# design.net
KiCad netlist of a schematic drawn in Altium Designer
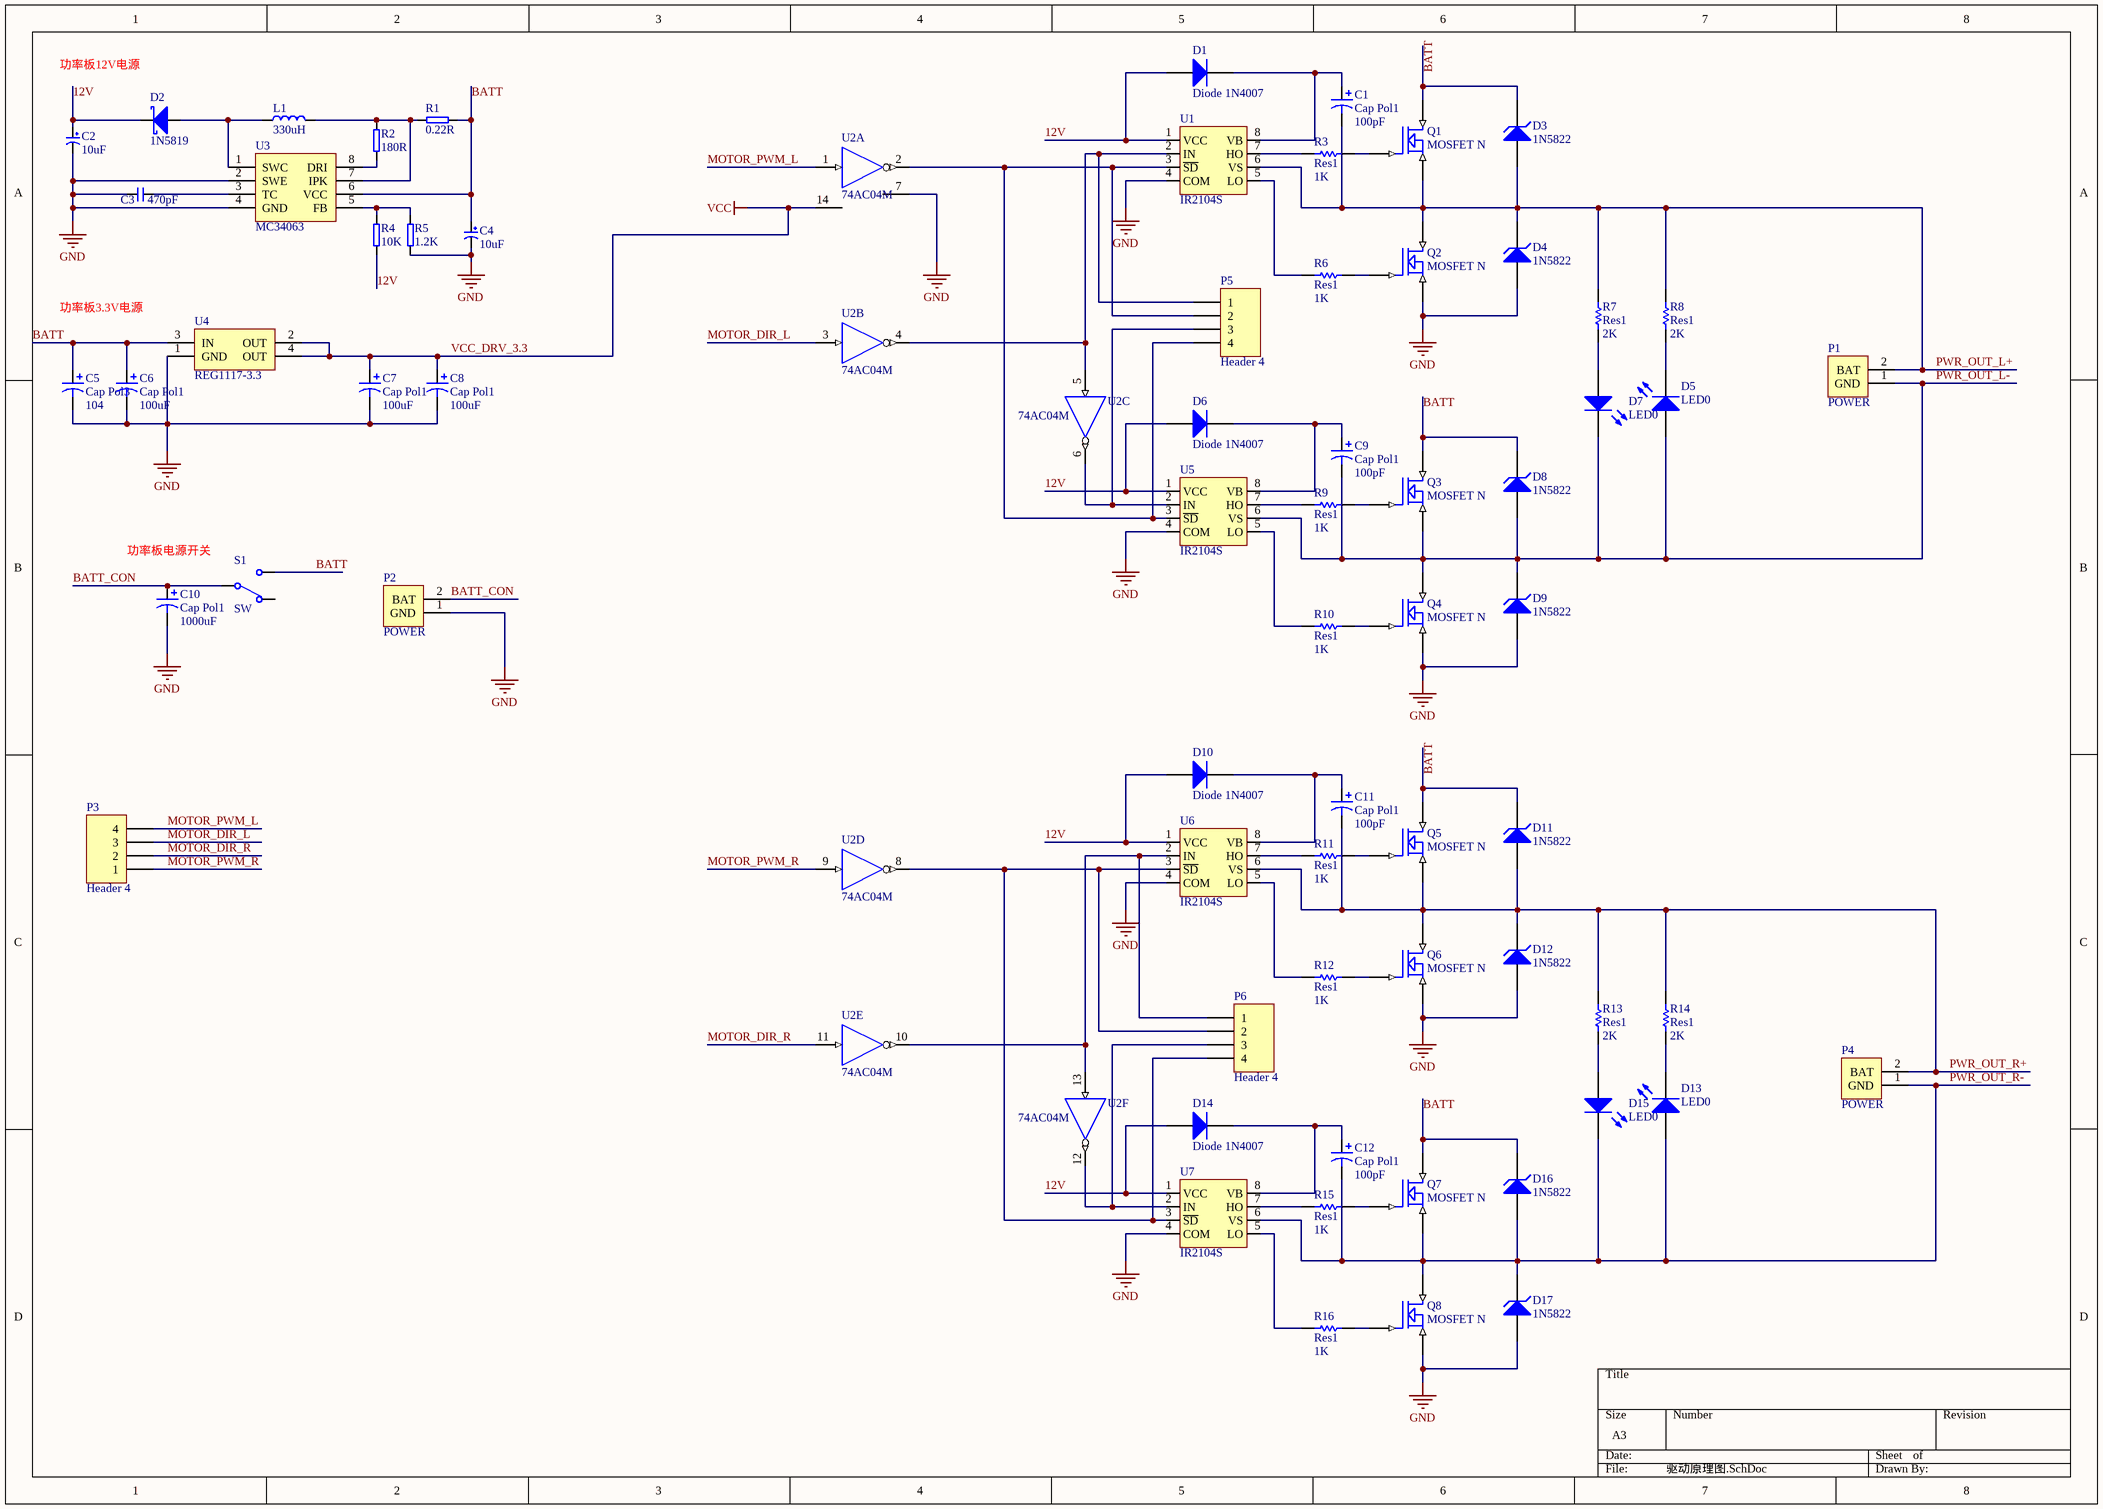
[diagram p0: 驱动原理图.SchDoc]

(export (version "E")
  (design (tool "Eeschema 10.0.6"))
  (components
    (comp (ref "C1")
      (value "Cap Pol1")
      (footprint "C0805")
      (description "Polarized Capacitor (Radial)")
      (fields (field (name "ALTIUM_VALUE") "100pF") (field (name "PUBLISHER") "Altium Limited"))
      (libsource (lib "Miscellaneous Devices") (part "Cap Pol1"))
    )
    (comp (ref "C2")
      (value "10uF")
      (footprint "3216-CAP-TA")
      (libsource (lib "2017elec_Library") (part "CAP_TA_3216"))
    )
    (comp (ref "C3")
      (value "470pF")
      (footprint "0603-CAP")
      (libsource (lib "2017elec_Library") (part "CAP_0603"))
    )
    (comp (ref "C4")
      (value "10uF")
      (footprint "3216-CAP-TA")
      (libsource (lib "2017elec_Library") (part "CAP_TA_3216"))
    )
    (comp (ref "C5")
      (value "Cap Pol3")
      (footprint "0805")
      (description "Polarized Capacitor (Surface Mount)")
      (fields (field (name "ALTIUM_VALUE") "104") (field (name "PUBLISHER") "Altium Limited"))
      (libsource (lib "Miscellaneous Devices") (part "Cap Pol3"))
    )
    (comp (ref "C6")
      (value "Cap Pol1")
      (footprint "RB.1/.2 - duplicate")
      (description "Polarized Capacitor (Radial)")
      (fields (field (name "ALTIUM_VALUE") "100uF") (field (name "PUBLISHER") "Altium Limited"))
      (libsource (lib "Miscellaneous Devices") (part "Cap Pol1"))
    )
    (comp (ref "C7")
      (value "Cap Pol1")
      (footprint "RB.1/.2 - duplicate")
      (description "Polarized Capacitor (Radial)")
      (fields (field (name "ALTIUM_VALUE") "100uF") (field (name "PUBLISHER") "Altium Limited"))
      (libsource (lib "Miscellaneous Devices") (part "Cap Pol1"))
    )
    (comp (ref "C8")
      (value "Cap Pol1")
      (footprint "RB.1/.2 - duplicate")
      (description "Polarized Capacitor (Radial)")
      (fields (field (name "ALTIUM_VALUE") "100uF") (field (name "PUBLISHER") "Altium Limited"))
      (libsource (lib "Miscellaneous Devices") (part "Cap Pol1"))
    )
    (comp (ref "C9")
      (value "Cap Pol1")
      (footprint "C0805")
      (description "Polarized Capacitor (Radial)")
      (fields (field (name "ALTIUM_VALUE") "100pF") (field (name "PUBLISHER") "Altium Limited"))
      (libsource (lib "Miscellaneous Devices") (part "Cap Pol1"))
    )
    (comp (ref "C10")
      (value "Cap Pol1")
      (footprint "CAPP")
      (description "Polarized Capacitor (Radial)")
      (fields (field (name "ALTIUM_VALUE") "1000uF") (field (name "PUBLISHER") "Altium Limited"))
      (libsource (lib "Miscellaneous Devices") (part "Cap Pol1"))
    )
    (comp (ref "C11")
      (value "Cap Pol1")
      (footprint "C0805")
      (description "Polarized Capacitor (Radial)")
      (fields (field (name "ALTIUM_VALUE") "100pF") (field (name "PUBLISHER") "Altium Limited"))
      (libsource (lib "Miscellaneous Devices") (part "Cap Pol1"))
    )
    (comp (ref "C12")
      (value "Cap Pol1")
      (footprint "C0805")
      (description "Polarized Capacitor (Radial)")
      (fields (field (name "ALTIUM_VALUE") "100pF") (field (name "PUBLISHER") "Altium Limited"))
      (libsource (lib "Miscellaneous Devices") (part "Cap Pol1"))
    )
    (comp (ref "D1")
      (value "Diode 1N4007")
      (footprint "DO-214AC(SMA)-SBD")
      (description "1 Amp General Purpose Rectifier")
      (fields (field (name "PUBLISHER") "Altium Limited"))
      (libsource (lib "Miscellaneous Devices") (part "Diode 1N4007"))
    )
    (comp (ref "D2")
      (value "1N5819")
      (footprint "DO-214AC(SMA)-SBD")
      (libsource (lib "2017elec_Library") (part "1N5819"))
    )
    (comp (ref "D3")
      (value "1N5822")
      (footprint "DO-214AC(SMA)-SBD")
      (description "One Watt Hermetically Sealed Glass Silicon Zener Diode")
      (fields (field (name "PUBLISHER") "Altium Limited"))
      (libsource (lib "Motorola Discrete Diode") (part "1N4760A"))
    )
    (comp (ref "D4")
      (value "1N5822")
      (footprint "DO-214AC(SMA)-SBD")
      (description "One Watt Hermetically Sealed Glass Silicon Zener Diode")
      (fields (field (name "PUBLISHER") "Altium Limited"))
      (libsource (lib "Motorola Discrete Diode") (part "1N4760A"))
    )
    (comp (ref "D5")
      (value "LED0")
      (footprint "3.5X2.8X1.9")
      (description "Typical INFRARED GaAs LED")
      (fields (field (name "PUBLISHER") "Altium Limited"))
      (libsource (lib "Miscellaneous Devices") (part "LED0"))
    )
    (comp (ref "D6")
      (value "Diode 1N4007")
      (footprint "DO-214AC(SMA)-SBD")
      (description "1 Amp General Purpose Rectifier")
      (fields (field (name "PUBLISHER") "Altium Limited"))
      (libsource (lib "Miscellaneous Devices") (part "Diode 1N4007"))
    )
    (comp (ref "D7")
      (value "LED0")
      (footprint "3.5X2.8X1.9")
      (description "Typical INFRARED GaAs LED")
      (fields (field (name "PUBLISHER") "Altium Limited"))
      (libsource (lib "Miscellaneous Devices") (part "LED0"))
    )
    (comp (ref "D8")
      (value "1N5822")
      (footprint "DO-214AC(SMA)-SBD")
      (description "One Watt Hermetically Sealed Glass Silicon Zener Diode")
      (fields (field (name "PUBLISHER") "Altium Limited"))
      (libsource (lib "Motorola Discrete Diode") (part "1N4760A"))
    )
    (comp (ref "D9")
      (value "1N5822")
      (footprint "DO-214AC(SMA)-SBD")
      (description "One Watt Hermetically Sealed Glass Silicon Zener Diode")
      (fields (field (name "PUBLISHER") "Altium Limited"))
      (libsource (lib "Motorola Discrete Diode") (part "1N4760A"))
    )
    (comp (ref "D10")
      (value "Diode 1N4007")
      (footprint "DO-214AC(SMA)-SBD")
      (description "1 Amp General Purpose Rectifier")
      (fields (field (name "PUBLISHER") "Altium Limited"))
      (libsource (lib "Miscellaneous Devices") (part "Diode 1N4007"))
    )
    (comp (ref "D11")
      (value "1N5822")
      (footprint "DO-214AC(SMA)-SBD")
      (description "One Watt Hermetically Sealed Glass Silicon Zener Diode")
      (fields (field (name "PUBLISHER") "Altium Limited"))
      (libsource (lib "Motorola Discrete Diode") (part "1N4760A"))
    )
    (comp (ref "D12")
      (value "1N5822")
      (footprint "DO-214AC(SMA)-SBD")
      (description "One Watt Hermetically Sealed Glass Silicon Zener Diode")
      (fields (field (name "PUBLISHER") "Altium Limited"))
      (libsource (lib "Motorola Discrete Diode") (part "1N4760A"))
    )
    (comp (ref "D13")
      (value "LED0")
      (footprint "3.5X2.8X1.9")
      (description "Typical INFRARED GaAs LED")
      (fields (field (name "PUBLISHER") "Altium Limited"))
      (libsource (lib "Miscellaneous Devices") (part "LED0"))
    )
    (comp (ref "D14")
      (value "Diode 1N4007")
      (footprint "DO-214AC(SMA)-SBD")
      (description "1 Amp General Purpose Rectifier")
      (fields (field (name "PUBLISHER") "Altium Limited"))
      (libsource (lib "Miscellaneous Devices") (part "Diode 1N4007"))
    )
    (comp (ref "D15")
      (value "LED0")
      (footprint "3.5X2.8X1.9")
      (description "Typical INFRARED GaAs LED")
      (fields (field (name "PUBLISHER") "Altium Limited"))
      (libsource (lib "Miscellaneous Devices") (part "LED0"))
    )
    (comp (ref "D16")
      (value "1N5822")
      (footprint "DO-214AC(SMA)-SBD")
      (description "One Watt Hermetically Sealed Glass Silicon Zener Diode")
      (fields (field (name "PUBLISHER") "Altium Limited"))
      (libsource (lib "Motorola Discrete Diode") (part "1N4760A"))
    )
    (comp (ref "D17")
      (value "1N5822")
      (footprint "DO-214AC(SMA)-SBD")
      (description "One Watt Hermetically Sealed Glass Silicon Zener Diode")
      (fields (field (name "PUBLISHER") "Altium Limited"))
      (libsource (lib "Motorola Discrete Diode") (part "1N4760A"))
    )
    (comp (ref "L1")
      (value "330uH")
      (footprint "Inductor_7*7*4")
      (libsource (lib "2017elec_Library") (part "inductor_7*7*4"))
    )
    (comp (ref "P1") (value "POWER") (footprint "POWER") (libsource (lib "2017elec_Library") (part "POWER")))
    (comp (ref "P2") (value "POWER") (footprint "POWER") (libsource (lib "2017elec_Library") (part "POWER")))
    (comp (ref "P3")
      (value "Header 4")
      (footprint "HDR1X4")
      (description "Header, 4-Pin")
      (fields (field (name "PUBLISHER") "Altium Limited"))
      (libsource (lib "Miscellaneous Connectors") (part "Header 4"))
    )
    (comp (ref "P4") (value "POWER") (footprint "POWER") (libsource (lib "2017elec_Library") (part "POWER")))
    (comp (ref "P5")
      (value "Header 4")
      (footprint "HDR1X4")
      (description "Header, 4-Pin")
      (fields (field (name "PUBLISHER") "Altium Limited"))
      (libsource (lib "") (part "Header 4_1"))
    )
    (comp (ref "P6")
      (value "Header 4")
      (footprint "HDR1X4")
      (description "Header, 4-Pin")
      (fields (field (name "PUBLISHER") "Altium Limited"))
      (libsource (lib "") (part "Header 4_1"))
    )
    (comp (ref "Q1") (value "MOSFET N") (footprint "TO-252") (libsource (lib "场效应管及可控硅") (part "MOSFET N")))
    (comp (ref "Q2") (value "MOSFET N") (footprint "TO-252") (libsource (lib "场效应管及可控硅") (part "MOSFET N")))
    (comp (ref "Q3") (value "MOSFET N") (footprint "TO-252") (libsource (lib "场效应管及可控硅") (part "MOSFET N")))
    (comp (ref "Q4") (value "MOSFET N") (footprint "TO-252") (libsource (lib "场效应管及可控硅") (part "MOSFET N")))
    (comp (ref "Q5") (value "MOSFET N") (footprint "TO-252") (libsource (lib "场效应管及可控硅") (part "MOSFET N")))
    (comp (ref "Q6") (value "MOSFET N") (footprint "TO-252") (libsource (lib "场效应管及可控硅") (part "MOSFET N")))
    (comp (ref "Q7") (value "MOSFET N") (footprint "TO-252") (libsource (lib "场效应管及可控硅") (part "MOSFET N")))
    (comp (ref "Q8") (value "MOSFET N") (footprint "TO-252") (libsource (lib "场效应管及可控硅") (part "MOSFET N")))
    (comp (ref "R1")
      (value "0.22R")
      (footprint "0603-RES")
      (libsource (lib "2017elec_Library") (part "RES_0603"))
    )
    (comp (ref "R2")
      (value "180R")
      (footprint "0603-RES")
      (libsource (lib "2017elec_Library") (part "RES_0603"))
    )
    (comp (ref "R3")
      (value "Res1")
      (footprint "0603-RES")
      (description "Resistor")
      (fields (field (name "ALTIUM_VALUE") "1K") (field (name "PUBLISHER") "Altium Limited"))
      (libsource (lib "Miscellaneous Devices") (part "Res1"))
    )
    (comp (ref "R4")
      (value "10K")
      (footprint "0603-RES")
      (libsource (lib "2017elec_Library") (part "RES_0603"))
    )
    (comp (ref "R5")
      (value "1.2K")
      (footprint "0603-RES")
      (libsource (lib "2017elec_Library") (part "RES_0603"))
    )
    (comp (ref "R6")
      (value "Res1")
      (footprint "0603-RES")
      (description "Resistor")
      (fields (field (name "ALTIUM_VALUE") "1K") (field (name "PUBLISHER") "Altium Limited"))
      (libsource (lib "Miscellaneous Devices") (part "Res1"))
    )
    (comp (ref "R7")
      (value "Res1")
      (footprint "0603-RES")
      (description "Resistor")
      (fields (field (name "ALTIUM_VALUE") "2K") (field (name "PUBLISHER") "Altium Limited"))
      (libsource (lib "Miscellaneous Devices") (part "Res1"))
    )
    (comp (ref "R8")
      (value "Res1")
      (footprint "0603-RES")
      (description "Resistor")
      (fields (field (name "ALTIUM_VALUE") "2K") (field (name "PUBLISHER") "Altium Limited"))
      (libsource (lib "Miscellaneous Devices") (part "Res1"))
    )
    (comp (ref "R9")
      (value "Res1")
      (footprint "0603-RES")
      (description "Resistor")
      (fields (field (name "ALTIUM_VALUE") "1K") (field (name "PUBLISHER") "Altium Limited"))
      (libsource (lib "Miscellaneous Devices") (part "Res1"))
    )
    (comp (ref "R10")
      (value "Res1")
      (footprint "0603-RES")
      (description "Resistor")
      (fields (field (name "ALTIUM_VALUE") "1K") (field (name "PUBLISHER") "Altium Limited"))
      (libsource (lib "Miscellaneous Devices") (part "Res1"))
    )
    (comp (ref "R11")
      (value "Res1")
      (footprint "0603-RES")
      (description "Resistor")
      (fields (field (name "ALTIUM_VALUE") "1K") (field (name "PUBLISHER") "Altium Limited"))
      (libsource (lib "Miscellaneous Devices") (part "Res1"))
    )
    (comp (ref "R12")
      (value "Res1")
      (footprint "0603-RES")
      (description "Resistor")
      (fields (field (name "ALTIUM_VALUE") "1K") (field (name "PUBLISHER") "Altium Limited"))
      (libsource (lib "Miscellaneous Devices") (part "Res1"))
    )
    (comp (ref "R13")
      (value "Res1")
      (footprint "0603-RES")
      (description "Resistor")
      (fields (field (name "ALTIUM_VALUE") "2K") (field (name "PUBLISHER") "Altium Limited"))
      (libsource (lib "Miscellaneous Devices") (part "Res1"))
    )
    (comp (ref "R14")
      (value "Res1")
      (footprint "0603-CAP")
      (description "Resistor")
      (fields (field (name "ALTIUM_VALUE") "2K") (field (name "PUBLISHER") "Altium Limited"))
      (libsource (lib "Miscellaneous Devices") (part "Res1"))
    )
    (comp (ref "R15")
      (value "Res1")
      (footprint "0603-RES")
      (description "Resistor")
      (fields (field (name "ALTIUM_VALUE") "1K") (field (name "PUBLISHER") "Altium Limited"))
      (libsource (lib "Miscellaneous Devices") (part "Res1"))
    )
    (comp (ref "R16")
      (value "Res1")
      (footprint "0603-RES")
      (description "Resistor")
      (fields (field (name "ALTIUM_VALUE") "1K") (field (name "PUBLISHER") "Altium Limited"))
      (libsource (lib "Miscellaneous Devices") (part "Res1"))
    )
    (comp (ref "S1") (value "SW") (footprint "SW") (libsource (lib "My K60") (part "SW")))
    (comp (ref "U1") (value "IR2104S") (footprint "SOIC-8") (libsource (lib "My K60") (part "IR2104S")))
    (comp (ref "U2")
      (value "74AC04M")
      (footprint "SO14_L")
      (description "Hex Inverter")
      (fields (field (name "PUBLISHER") "Altium Limited"))
      (libsource (lib "ST Logic Gate") (part "74AC04M"))
    )
    (comp (ref "U3")
      (value "MC34063")
      (footprint "SOP-8")
      (libsource (lib "2017elec_Library") (part "MC34063"))
    )
    (comp (ref "U4")
      (value "REG1117-3.3")
      (footprint "ZZ311")
      (description "800mA and 1A Low Dropout Positive Regulator 2.85V, 3.3V, 5V, and Adjustable")
      (fields (field (name "PUBLISHER") "Altium Limited"))
      (libsource (lib "BB Power Mgt Voltage Regulator") (part "REG1117-3.3"))
    )
    (comp (ref "U5") (value "IR2104S") (footprint "SOIC-8") (libsource (lib "My K60") (part "IR2104S")))
    (comp (ref "U6") (value "IR2104S") (footprint "SOIC-8") (libsource (lib "My K60") (part "IR2104S")))
    (comp (ref "U7") (value "IR2104S") (footprint "SOIC-8") (libsource (lib "My K60") (part "IR2104S")))
  )
  (nets
    (net (code "1") (name "/12V") (class "Default")
      (node (ref "C2") (pin "1") (pinfunction "1_1") (pintype "passive"))
      (node (ref "D1") (pin "1") (pinfunction "A_1") (pintype "passive"))
      (node (ref "D10") (pin "1") (pinfunction "A_1") (pintype "passive"))
      (node (ref "D14") (pin "1") (pinfunction "A_1") (pintype "passive"))
      (node (ref "D2") (pin "2") (pinfunction "K_2") (pintype "passive"))
      (node (ref "D6") (pin "1") (pinfunction "A_1") (pintype "passive"))
      (node (ref "R4") (pin "1") (pinfunction "1_1") (pintype "passive"))
      (node (ref "U1") (pin "1") (pinfunction "VCC_1") (pintype "passive"))
      (node (ref "U5") (pin "1") (pinfunction "VCC_1") (pintype "passive"))
      (node (ref "U6") (pin "1") (pinfunction "VCC_1") (pintype "passive"))
      (node (ref "U7") (pin "1") (pinfunction "VCC_1") (pintype "passive"))
    )
    (net (code "2") (name "/BATT") (class "Default")
      (node (ref "C4") (pin "1") (pinfunction "1_1") (pintype "passive"))
      (node (ref "C5") (pin "1") (pinfunction "1_1") (pintype "passive"))
      (node (ref "C6") (pin "1") (pinfunction "1_1") (pintype "passive"))
      (node (ref "D16") (pin "2") (pinfunction "K_2") (pintype "passive"))
      (node (ref "D8") (pin "2") (pinfunction "K_2") (pintype "passive"))
      (node (ref "Q3") (pin "2") (pinfunction "D_2") (pintype "input"))
      (node (ref "Q7") (pin "2") (pinfunction "D_2") (pintype "input"))
      (node (ref "R1") (pin "2") (pinfunction "2_2") (pintype "passive"))
      (node (ref "S1") (pin "3") (pinfunction "3_3") (pintype "passive"))
      (node (ref "U3") (pin "6") (pinfunction "VCC_6") (pintype "passive"))
      (node (ref "U4") (pin "3") (pinfunction "IN_3") (pintype "power_in"))
    )
    (net (code "3") (name "/BATT_CON") (class "Default")
      (node (ref "C10") (pin "1") (pinfunction "1_1") (pintype "passive"))
      (node (ref "P2") (pin "2") (pinfunction "BAT_2") (pintype "passive"))
      (node (ref "S1") (pin "2") (pinfunction "2_2") (pintype "passive"))
    )
    (net (code "4") (name "/MOTOR_DIR_L") (class "Default")
      (node (ref "P3") (pin "3") (pinfunction "3_3") (pintype "passive"))
      (node (ref "U2") (pin "3") (pinfunction "A_3") (pintype "input"))
    )
    (net (code "5") (name "/MOTOR_DIR_R") (class "Default")
      (node (ref "P3") (pin "2") (pinfunction "2_2") (pintype "passive"))
      (node (ref "U2") (pin "11") (pinfunction "A_11") (pintype "input"))
    )
    (net (code "6") (name "/MOTOR_PWM_L") (class "Default")
      (node (ref "P3") (pin "4") (pinfunction "4_4") (pintype "passive"))
      (node (ref "U2") (pin "1") (pinfunction "A_1") (pintype "input"))
    )
    (net (code "7") (name "/MOTOR_PWM_R") (class "Default")
      (node (ref "P3") (pin "1") (pinfunction "1_1") (pintype "passive"))
      (node (ref "U2") (pin "9") (pinfunction "A_9") (pintype "input"))
    )
    (net (code "8") (name "/PWR_OUT_L+") (class "Default")
      (node (ref "C1") (pin "2") (pinfunction "2_2") (pintype "passive"))
      (node (ref "D3") (pin "1") (pinfunction "A_1") (pintype "passive"))
      (node (ref "D4") (pin "2") (pinfunction "K_2") (pintype "passive"))
      (node (ref "P1") (pin "2") (pinfunction "BAT_2") (pintype "passive"))
      (node (ref "Q1") (pin "3") (pinfunction "S_3") (pintype "input"))
      (node (ref "Q2") (pin "2") (pinfunction "D_2") (pintype "input"))
      (node (ref "R7") (pin "2") (pinfunction "2_2") (pintype "passive"))
      (node (ref "R8") (pin "2") (pinfunction "2_2") (pintype "passive"))
      (node (ref "U1") (pin "6") (pinfunction "VS_6") (pintype "passive"))
    )
    (net (code "9") (name "/PWR_OUT_L-") (class "Default")
      (node (ref "C9") (pin "2") (pinfunction "2_2") (pintype "passive"))
      (node (ref "D5") (pin "1") (pinfunction "A_1") (pintype "passive"))
      (node (ref "D7") (pin "2") (pinfunction "K_2") (pintype "passive"))
      (node (ref "D8") (pin "1") (pinfunction "A_1") (pintype "passive"))
      (node (ref "D9") (pin "2") (pinfunction "K_2") (pintype "passive"))
      (node (ref "P1") (pin "1") (pinfunction "GND_1") (pintype "passive"))
      (node (ref "Q3") (pin "3") (pinfunction "S_3") (pintype "input"))
      (node (ref "Q4") (pin "2") (pinfunction "D_2") (pintype "input"))
      (node (ref "U5") (pin "6") (pinfunction "VS_6") (pintype "passive"))
    )
    (net (code "10") (name "/PWR_OUT_R+") (class "Default")
      (node (ref "C11") (pin "2") (pinfunction "2_2") (pintype "passive"))
      (node (ref "D11") (pin "1") (pinfunction "A_1") (pintype "passive"))
      (node (ref "D12") (pin "2") (pinfunction "K_2") (pintype "passive"))
      (node (ref "P4") (pin "2") (pinfunction "BAT_2") (pintype "passive"))
      (node (ref "Q5") (pin "3") (pinfunction "S_3") (pintype "input"))
      (node (ref "Q6") (pin "2") (pinfunction "D_2") (pintype "input"))
      (node (ref "R13") (pin "2") (pinfunction "2_2") (pintype "passive"))
      (node (ref "R14") (pin "2") (pinfunction "2_2") (pintype "passive"))
      (node (ref "U6") (pin "6") (pinfunction "VS_6") (pintype "passive"))
    )
    (net (code "11") (name "/PWR_OUT_R-") (class "Default")
      (node (ref "C12") (pin "2") (pinfunction "2_2") (pintype "passive"))
      (node (ref "D13") (pin "1") (pinfunction "A_1") (pintype "passive"))
      (node (ref "D15") (pin "2") (pinfunction "K_2") (pintype "passive"))
      (node (ref "D16") (pin "1") (pinfunction "A_1") (pintype "passive"))
      (node (ref "D17") (pin "2") (pinfunction "K_2") (pintype "passive"))
      (node (ref "P4") (pin "1") (pinfunction "GND_1") (pintype "passive"))
      (node (ref "Q7") (pin "3") (pinfunction "S_3") (pintype "input"))
      (node (ref "Q8") (pin "2") (pinfunction "D_2") (pintype "input"))
      (node (ref "U7") (pin "6") (pinfunction "VS_6") (pintype "passive"))
    )
    (net (code "12") (name "GND") (class "Default")
      (node (ref "C10") (pin "2") (pinfunction "2_2") (pintype "passive"))
      (node (ref "C2") (pin "2") (pinfunction "2_2") (pintype "passive"))
      (node (ref "C3") (pin "1") (pinfunction "1_1") (pintype "passive"))
      (node (ref "C4") (pin "2") (pinfunction "2_2") (pintype "passive"))
      (node (ref "C5") (pin "2") (pinfunction "2_2") (pintype "passive"))
      (node (ref "C6") (pin "2") (pinfunction "2_2") (pintype "passive"))
      (node (ref "C7") (pin "2") (pinfunction "2_2") (pintype "passive"))
      (node (ref "C8") (pin "2") (pinfunction "2_2") (pintype "passive"))
      (node (ref "D12") (pin "1") (pinfunction "A_1") (pintype "passive"))
      (node (ref "D17") (pin "1") (pinfunction "A_1") (pintype "passive"))
      (node (ref "D4") (pin "1") (pinfunction "A_1") (pintype "passive"))
      (node (ref "D9") (pin "1") (pinfunction "A_1") (pintype "passive"))
      (node (ref "P2") (pin "1") (pinfunction "GND_1") (pintype "passive"))
      (node (ref "Q2") (pin "3") (pinfunction "S_3") (pintype "input"))
      (node (ref "Q4") (pin "3") (pinfunction "S_3") (pintype "input"))
      (node (ref "Q6") (pin "3") (pinfunction "S_3") (pintype "input"))
      (node (ref "Q8") (pin "3") (pinfunction "S_3") (pintype "input"))
      (node (ref "R5") (pin "1") (pinfunction "1_1") (pintype "passive"))
      (node (ref "U1") (pin "4") (pinfunction "COM_4") (pintype "passive"))
      (node (ref "U2") (pin "7") (pinfunction "GND_7") (pintype "power_in"))
      (node (ref "U3") (pin "2") (pinfunction "SWE_2") (pintype "passive"))
      (node (ref "U3") (pin "4") (pinfunction "GND_4") (pintype "passive"))
      (node (ref "U4") (pin "1") (pinfunction "GND_1") (pintype "power_in"))
      (node (ref "U5") (pin "4") (pinfunction "COM_4") (pintype "passive"))
      (node (ref "U6") (pin "4") (pinfunction "COM_4") (pintype "passive"))
      (node (ref "U7") (pin "4") (pinfunction "COM_4") (pintype "passive"))
    )
    (net (code "13") (name "Net-(D1-K)") (class "Default")
      (node (ref "C1") (pin "1") (pinfunction "1_1") (pintype "passive"))
      (node (ref "D1") (pin "2") (pinfunction "K_2") (pintype "passive"))
      (node (ref "U1") (pin "8") (pinfunction "VB_8") (pintype "passive"))
    )
    (net (code "14") (name "Net-(D2-A)") (class "Default")
      (node (ref "D2") (pin "1") (pinfunction "A_1") (pintype "passive"))
      (node (ref "L1") (pin "1") (pinfunction "1_1") (pintype "passive"))
      (node (ref "U3") (pin "1") (pinfunction "SWC_1") (pintype "passive"))
    )
    (net (code "15") (name "Net-(D3-K)") (class "Default")
      (node (ref "D3") (pin "2") (pinfunction "K_2") (pintype "passive"))
      (node (ref "Q1") (pin "2") (pinfunction "D_2") (pintype "input"))
    )
    (net (code "16") (name "Net-(D5-K)") (class "Default")
      (node (ref "D5") (pin "2") (pinfunction "K_2") (pintype "passive"))
      (node (ref "R8") (pin "1") (pinfunction "1_1") (pintype "passive"))
    )
    (net (code "17") (name "Net-(D6-K)") (class "Default")
      (node (ref "C9") (pin "1") (pinfunction "1_1") (pintype "passive"))
      (node (ref "D6") (pin "2") (pinfunction "K_2") (pintype "passive"))
      (node (ref "U5") (pin "8") (pinfunction "VB_8") (pintype "passive"))
    )
    (net (code "18") (name "Net-(D7-A)") (class "Default")
      (node (ref "D7") (pin "1") (pinfunction "A_1") (pintype "passive"))
      (node (ref "R7") (pin "1") (pinfunction "1_1") (pintype "passive"))
    )
    (net (code "19") (name "Net-(D10-K)") (class "Default")
      (node (ref "C11") (pin "1") (pinfunction "1_1") (pintype "passive"))
      (node (ref "D10") (pin "2") (pinfunction "K_2") (pintype "passive"))
      (node (ref "U6") (pin "8") (pinfunction "VB_8") (pintype "passive"))
    )
    (net (code "20") (name "Net-(D11-K)") (class "Default")
      (node (ref "D11") (pin "2") (pinfunction "K_2") (pintype "passive"))
      (node (ref "Q5") (pin "2") (pinfunction "D_2") (pintype "input"))
    )
    (net (code "21") (name "Net-(D13-K)") (class "Default")
      (node (ref "D13") (pin "2") (pinfunction "K_2") (pintype "passive"))
      (node (ref "R14") (pin "1") (pinfunction "1_1") (pintype "passive"))
    )
    (net (code "22") (name "Net-(D14-K)") (class "Default")
      (node (ref "C12") (pin "1") (pinfunction "1_1") (pintype "passive"))
      (node (ref "D14") (pin "2") (pinfunction "K_2") (pintype "passive"))
      (node (ref "U7") (pin "8") (pinfunction "VB_8") (pintype "passive"))
    )
    (net (code "23") (name "Net-(D15-A)") (class "Default")
      (node (ref "D15") (pin "1") (pinfunction "A_1") (pintype "passive"))
      (node (ref "R13") (pin "1") (pinfunction "1_1") (pintype "passive"))
    )
    (net (code "24") (name "Net-(Q1-G)") (class "Default")
      (node (ref "Q1") (pin "1") (pinfunction "G_1") (pintype "input"))
      (node (ref "R3") (pin "2") (pinfunction "2_2") (pintype "passive"))
    )
    (net (code "25") (name "Net-(Q2-G)") (class "Default")
      (node (ref "Q2") (pin "1") (pinfunction "G_1") (pintype "input"))
      (node (ref "R6") (pin "2") (pinfunction "2_2") (pintype "passive"))
    )
    (net (code "26") (name "Net-(Q3-G)") (class "Default")
      (node (ref "Q3") (pin "1") (pinfunction "G_1") (pintype "input"))
      (node (ref "R9") (pin "2") (pinfunction "2_2") (pintype "passive"))
    )
    (net (code "27") (name "Net-(Q4-G)") (class "Default")
      (node (ref "Q4") (pin "1") (pinfunction "G_1") (pintype "input"))
      (node (ref "R10") (pin "2") (pinfunction "2_2") (pintype "passive"))
    )
    (net (code "28") (name "Net-(Q5-G)") (class "Default")
      (node (ref "Q5") (pin "1") (pinfunction "G_1") (pintype "input"))
      (node (ref "R11") (pin "2") (pinfunction "2_2") (pintype "passive"))
    )
    (net (code "29") (name "Net-(Q6-G)") (class "Default")
      (node (ref "Q6") (pin "1") (pinfunction "G_1") (pintype "input"))
      (node (ref "R12") (pin "2") (pinfunction "2_2") (pintype "passive"))
    )
    (net (code "30") (name "Net-(Q7-G)") (class "Default")
      (node (ref "Q7") (pin "1") (pinfunction "G_1") (pintype "input"))
      (node (ref "R15") (pin "2") (pinfunction "2_2") (pintype "passive"))
    )
    (net (code "31") (name "Net-(Q8-G)") (class "Default")
      (node (ref "Q8") (pin "1") (pinfunction "G_1") (pintype "input"))
      (node (ref "R16") (pin "2") (pinfunction "2_2") (pintype "passive"))
    )
    (net (code "32") (name "Net-(U1-HO)") (class "Default")
      (node (ref "R3") (pin "1") (pinfunction "1_1") (pintype "passive"))
      (node (ref "U1") (pin "7") (pinfunction "HO_7") (pintype "passive"))
    )
    (net (code "33") (name "Net-(U1-IN)") (class "Default")
      (node (ref "P5") (pin "1") (pinfunction "1_1") (pintype "passive"))
      (node (ref "U1") (pin "2") (pinfunction "IN_2") (pintype "passive"))
      (node (ref "U2") (pin "4") (pinfunction "Y_4") (pintype "output"))
      (node (ref "U2") (pin "5") (pinfunction "A_5") (pintype "input"))
    )
    (net (code "34") (name "Net-(U1-LO)") (class "Default")
      (node (ref "R6") (pin "1") (pinfunction "1_1") (pintype "passive"))
      (node (ref "U1") (pin "5") (pinfunction "LO_5") (pintype "passive"))
    )
    (net (code "35") (name "Net-(U1-~{SD})") (class "Default")
      (node (ref "P5") (pin "2") (pinfunction "2_2") (pintype "passive"))
      (node (ref "P5") (pin "4") (pinfunction "4_4") (pintype "passive"))
      (node (ref "U1") (pin "3") (pinfunction "~{SD}_3") (pintype "passive"))
      (node (ref "U2") (pin "2") (pinfunction "Y_2") (pintype "output"))
      (node (ref "U5") (pin "3") (pinfunction "~{SD}_3") (pintype "passive"))
    )
    (net (code "36") (name "Net-(U2C-Y)") (class "Default")
      (node (ref "P5") (pin "3") (pinfunction "3_3") (pintype "passive"))
      (node (ref "U2") (pin "6") (pinfunction "Y_6") (pintype "output"))
      (node (ref "U5") (pin "2") (pinfunction "IN_2") (pintype "passive"))
    )
    (net (code "37") (name "Net-(U2D-Y)") (class "Default")
      (node (ref "P6") (pin "2") (pinfunction "2_2") (pintype "passive"))
      (node (ref "P6") (pin "4") (pinfunction "4_4") (pintype "passive"))
      (node (ref "U2") (pin "8") (pinfunction "Y_8") (pintype "output"))
      (node (ref "U6") (pin "3") (pinfunction "~{SD}_3") (pintype "passive"))
      (node (ref "U7") (pin "3") (pinfunction "~{SD}_3") (pintype "passive"))
    )
    (net (code "38") (name "Net-(U2E-Y)") (class "Default")
      (node (ref "P6") (pin "1") (pinfunction "1_1") (pintype "passive"))
      (node (ref "U2") (pin "10") (pinfunction "Y_10") (pintype "output"))
      (node (ref "U2") (pin "13") (pinfunction "A_13") (pintype "input"))
      (node (ref "U6") (pin "2") (pinfunction "IN_2") (pintype "passive"))
    )
    (net (code "39") (name "Net-(U2F-Y)") (class "Default")
      (node (ref "P6") (pin "3") (pinfunction "3_3") (pintype "passive"))
      (node (ref "U2") (pin "12") (pinfunction "Y_12") (pintype "output"))
      (node (ref "U7") (pin "2") (pinfunction "IN_2") (pintype "passive"))
    )
    (net (code "40") (name "Net-(U3-DRI)") (class "Default")
      (node (ref "R2") (pin "1") (pinfunction "1_1") (pintype "passive"))
      (node (ref "U3") (pin "8") (pinfunction "DRI_8") (pintype "passive"))
    )
    (net (code "41") (name "Net-(U3-FB)") (class "Default")
      (node (ref "R4") (pin "2") (pinfunction "2_2") (pintype "passive"))
      (node (ref "R5") (pin "2") (pinfunction "2_2") (pintype "passive"))
      (node (ref "U3") (pin "5") (pinfunction "FB_5") (pintype "passive"))
    )
    (net (code "42") (name "Net-(U3-IPK)") (class "Default")
      (node (ref "L1") (pin "2") (pinfunction "2_2") (pintype "passive"))
      (node (ref "R1") (pin "1") (pinfunction "1_1") (pintype "passive"))
      (node (ref "R2") (pin "2") (pinfunction "2_2") (pintype "passive"))
      (node (ref "U3") (pin "7") (pinfunction "IPK_7") (pintype "passive"))
    )
    (net (code "43") (name "Net-(U3-TC)") (class "Default")
      (node (ref "C3") (pin "2") (pinfunction "2_2") (pintype "passive"))
      (node (ref "U3") (pin "3") (pinfunction "TC_3") (pintype "passive"))
    )
    (net (code "44") (name "Net-(U5-HO)") (class "Default")
      (node (ref "R9") (pin "1") (pinfunction "1_1") (pintype "passive"))
      (node (ref "U5") (pin "7") (pinfunction "HO_7") (pintype "passive"))
    )
    (net (code "45") (name "Net-(U5-LO)") (class "Default")
      (node (ref "R10") (pin "1") (pinfunction "1_1") (pintype "passive"))
      (node (ref "U5") (pin "5") (pinfunction "LO_5") (pintype "passive"))
    )
    (net (code "46") (name "Net-(U6-HO)") (class "Default")
      (node (ref "R11") (pin "1") (pinfunction "1_1") (pintype "passive"))
      (node (ref "U6") (pin "7") (pinfunction "HO_7") (pintype "passive"))
    )
    (net (code "47") (name "Net-(U6-LO)") (class "Default")
      (node (ref "R12") (pin "1") (pinfunction "1_1") (pintype "passive"))
      (node (ref "U6") (pin "5") (pinfunction "LO_5") (pintype "passive"))
    )
    (net (code "48") (name "Net-(U7-HO)") (class "Default")
      (node (ref "R15") (pin "1") (pinfunction "1_1") (pintype "passive"))
      (node (ref "U7") (pin "7") (pinfunction "HO_7") (pintype "passive"))
    )
    (net (code "49") (name "Net-(U7-LO)") (class "Default")
      (node (ref "R16") (pin "1") (pinfunction "1_1") (pintype "passive"))
      (node (ref "U7") (pin "5") (pinfunction "LO_5") (pintype "passive"))
    )
    (net (code "50") (name "VCC") (class "Default")
      (node (ref "C7") (pin "1") (pinfunction "1_1") (pintype "passive"))
      (node (ref "C8") (pin "1") (pinfunction "1_1") (pintype "passive"))
      (node (ref "U2") (pin "14") (pinfunction "VCC_14") (pintype "power_in"))
      (node (ref "U4") (pin "2") (pinfunction "OUT_2") (pintype "power_in"))
      (node (ref "U4") (pin "4") (pinfunction "OUT_4") (pintype "power_in"))
    )
    (net (code "51") (name "unconnected-(S1-Pad1)") (class "Default")
      (node (ref "S1") (pin "1") (pinfunction "1_1") (pintype "passive"))
    )
  )
)
